# Sheet1.net
KiCad netlist of a schematic drawn in Altium Designer
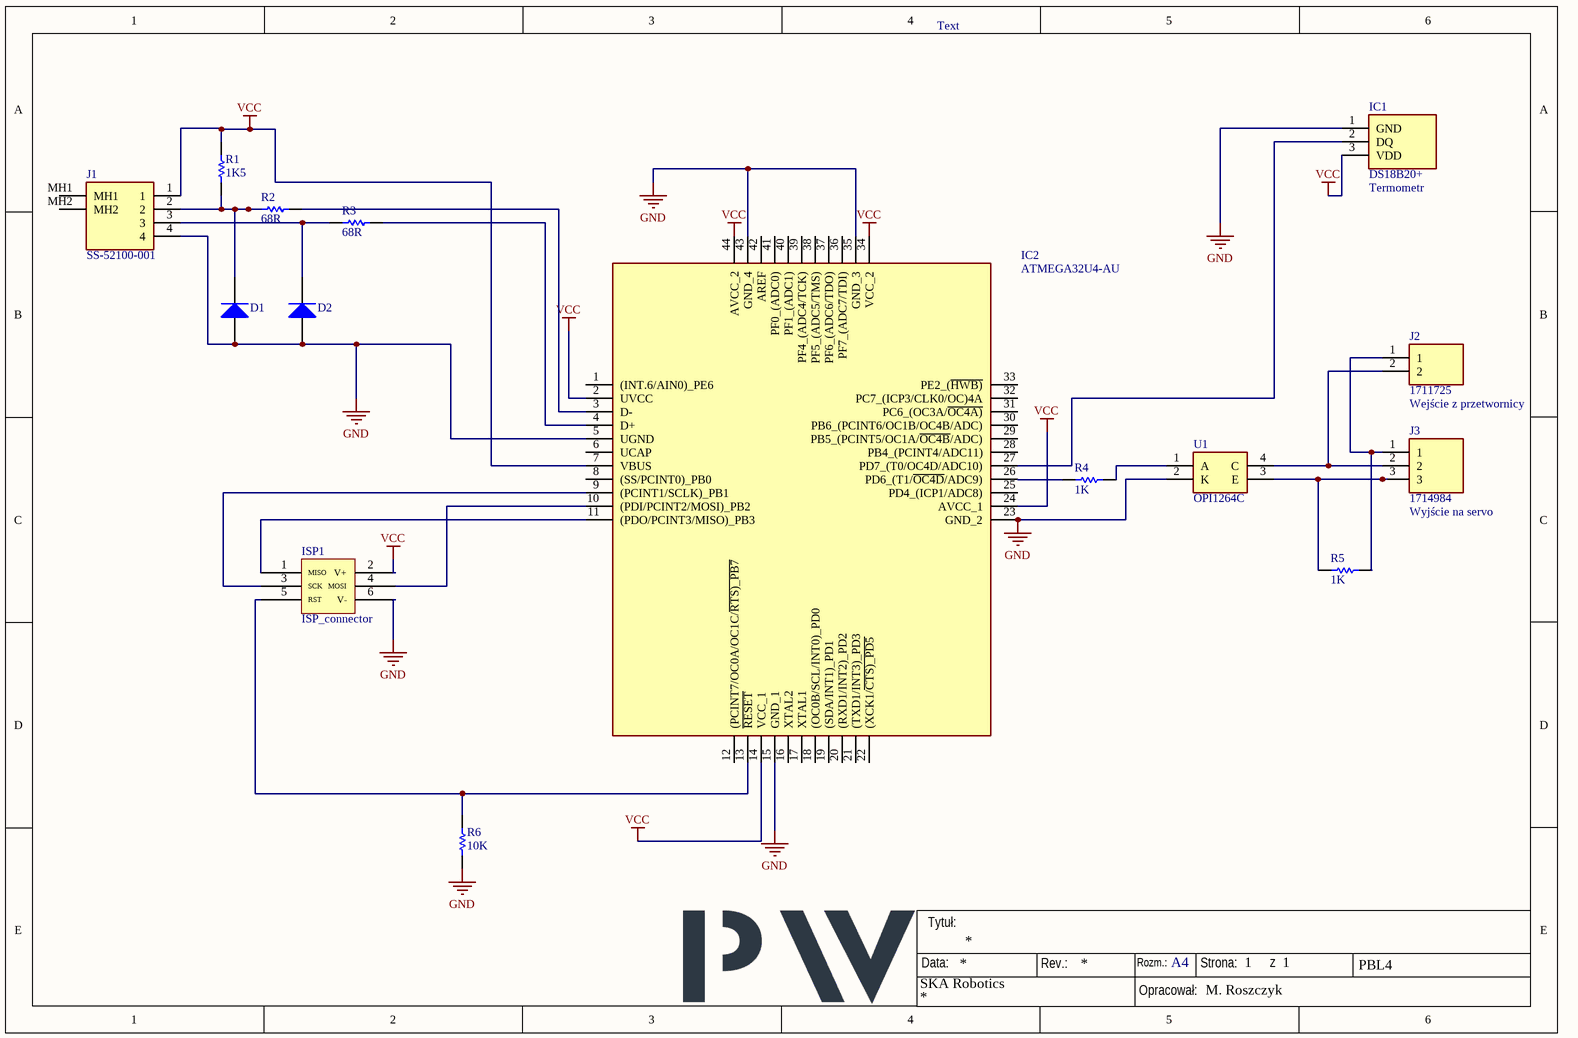
[diagram p0: Sheet1.SchDoc]

(export (version "E")
  (design (tool "Eeschema 10.0.6"))
  (components
    (comp (ref "D1") (value "Diode") (libsource (lib "Simulation Generic Components") (part "Diode")))
    (comp (ref "D2") (value "Diode") (libsource (lib "Simulation Generic Components") (part "Diode")))
    (comp (ref "IC1")
      (value "DS18B20+")
      (footprint "SamacSys:DS18B20")
      (description "Integrated Circuit")
      (fields (field (name "MOUSER PART NUMBER") "700-DS18B20+"))
      (libsource (lib "*") (part "DS18B20+"))
    )
    (comp (ref "IC2")
      (value "ATMEGA32U4-AU")
      (footprint "SamacSys:QFP80P1200X1200X120-44N")
      (description "Integrated Circuit")
      (fields (field (name "MOUSER PART NUMBER") "556-ATMEGA32U4-AU"))
      (libsource (lib "*") (part "ATMEGA32U4-AU"))
    )
    (comp (ref "ISP1") (value "ISP_connector") (libsource (lib "chwytak-schlib") (part "ISP_connector")))
    (comp (ref "J1")
      (value "SS-52100-001")
      (footprint "SamacSys:SS52100001")
      (description "Connector")
      (fields (field (name "MOUSER PART NUMBER") "530-SS-52100-001"))
      (libsource (lib "*") (part "SS-52100-001"))
    )
    (comp (ref "J2")
      (value "1711725")
      (footprint "SamacSys:1711725")
      (description "Connector")
      (fields (field (name "MOUSER PART NUMBER") "651-1711725"))
      (libsource (lib "*") (part "1711725"))
    )
    (comp (ref "J3")
      (value "1714984")
      (footprint "SamacSys:1714984")
      (description "Connector")
      (fields (field (name "MOUSER PART NUMBER") "651-1714984"))
      (libsource (lib "*") (part "1714984"))
    )
    (comp (ref "R1")
      (value "1K5")
      (description "Resistor")
      (libsource (lib "Simulation Generic Components") (part "Resistor"))
    )
    (comp (ref "R2")
      (value "68R")
      (description "Resistor")
      (libsource (lib "Simulation Generic Components") (part "Resistor"))
    )
    (comp (ref "R3")
      (value "68R")
      (description "Resistor")
      (libsource (lib "Simulation Generic Components") (part "Resistor"))
    )
    (comp (ref "R4")
      (value "1K")
      (description "Resistor")
      (libsource (lib "Simulation Generic Components") (part "Resistor"))
    )
    (comp (ref "R5")
      (value "1K")
      (description "Resistor")
      (libsource (lib "Simulation Generic Components") (part "Resistor"))
    )
    (comp (ref "R6")
      (value "10K")
      (footprint "AXIAL-0.3")
      (description "Resistor")
      (fields (field (name "PUBLISHER") "Altium Limited"))
      (libsource (lib "Miscellaneous Devices") (part "Res1"))
    )
    (comp (ref "U1")
      (value "OPI1264C")
      (footprint "SamacSys:OPI1264C")
      (description "Undefined or Miscellaneous")
      (fields (field (name "MOUSER PART NUMBER") "828-OPI1264C"))
      (libsource (lib "*") (part "OPI1264C"))
    )
  )
  (nets
    (net (code "1") (name "GND") (class "Default")
      (node (ref "D1") (pin "1") (pinfunction "A_1") (pintype "passive"))
      (node (ref "D2") (pin "1") (pinfunction "A_1") (pintype "passive"))
      (node (ref "IC1") (pin "1") (pinfunction "GND_1") (pintype "passive"))
      (node (ref "IC2") (pin "15") (pinfunction "GND_1_15") (pintype "passive"))
      (node (ref "IC2") (pin "23") (pinfunction "GND_2_23") (pintype "passive"))
      (node (ref "IC2") (pin "35") (pinfunction "GND_3_35") (pintype "passive"))
      (node (ref "IC2") (pin "43") (pinfunction "GND_4_43") (pintype "passive"))
      (node (ref "IC2") (pin "5") (pinfunction "UGND_5") (pintype "passive"))
      (node (ref "ISP1") (pin "6") (pinfunction "V-_6") (pintype "passive"))
      (node (ref "J1") (pin "4") (pinfunction "4_4") (pintype "passive"))
      (node (ref "R6") (pin "1") (pinfunction "1_1") (pintype "passive"))
      (node (ref "U1") (pin "2") (pinfunction "K_2") (pintype "passive"))
    )
    (net (code "2") (name "Net-(D1-K)") (class "Default")
      (node (ref "D1") (pin "2") (pinfunction "K_2") (pintype "passive"))
      (node (ref "J1") (pin "2") (pinfunction "2_2") (pintype "passive"))
      (node (ref "R1") (pin "1") (pinfunction "1_1") (pintype "passive"))
      (node (ref "R2") (pin "1") (pinfunction "1_1") (pintype "passive"))
    )
    (net (code "3") (name "Net-(D2-K)") (class "Default")
      (node (ref "D2") (pin "2") (pinfunction "K_2") (pintype "passive"))
      (node (ref "J1") (pin "3") (pinfunction "3_3") (pintype "passive"))
      (node (ref "R3") (pin "1") (pinfunction "1_1") (pintype "passive"))
    )
    (net (code "4") (name "Net-(IC1-DQ)") (class "Default")
      (node (ref "IC1") (pin "2") (pinfunction "DQ_2") (pintype "passive"))
      (node (ref "IC2") (pin "27") (pinfunction "PD7_(T0/OC4D/ADC10)_27") (pintype "passive"))
    )
    (net (code "5") (name "Net-(IC2-(PCINT1{slash}SCLK)_PB1)") (class "Default")
      (node (ref "IC2") (pin "9") (pinfunction "(PCINT1/SCLK)_PB1_9") (pintype "passive"))
      (node (ref "ISP1") (pin "3") (pinfunction "SCK_3") (pintype "passive"))
    )
    (net (code "6") (name "Net-(IC2-(PDI{slash}PCINT2{slash}MOSI)_PB2)") (class "Default")
      (node (ref "IC2") (pin "10") (pinfunction "(PDI/PCINT2/MOSI)_PB2_10") (pintype "passive"))
      (node (ref "ISP1") (pin "4") (pinfunction "MOSI_4") (pintype "passive"))
    )
    (net (code "7") (name "Net-(IC2-(PDO{slash}PCINT3{slash}MISO)_PB3)") (class "Default")
      (node (ref "IC2") (pin "11") (pinfunction "(PDO/PCINT3/MISO)_PB3_11") (pintype "passive"))
      (node (ref "ISP1") (pin "1") (pinfunction "MISO_1") (pintype "passive"))
    )
    (net (code "8") (name "Net-(IC2-D+)") (class "Default")
      (node (ref "IC2") (pin "4") (pinfunction "D+_4") (pintype "passive"))
      (node (ref "R3") (pin "2") (pinfunction "2_2") (pintype "passive"))
    )
    (net (code "9") (name "Net-(IC2-D-)") (class "Default")
      (node (ref "IC2") (pin "3") (pinfunction "D-_3") (pintype "passive"))
      (node (ref "R2") (pin "2") (pinfunction "2_2") (pintype "passive"))
    )
    (net (code "10") (name "Net-(IC2-PD6_(T1{slash}~{OC4D}{slash}ADC9))") (class "Default")
      (node (ref "IC2") (pin "26") (pinfunction "PD6_(T1/~{OC4D}/ADC9)_26") (pintype "passive"))
      (node (ref "R4") (pin "1") (pinfunction "1_1") (pintype "passive"))
    )
    (net (code "11") (name "Net-(IC2-~{RESET})") (class "Default")
      (node (ref "IC2") (pin "13") (pinfunction "~{RESET}_13") (pintype "passive"))
      (node (ref "ISP1") (pin "5") (pinfunction "RST_5") (pintype "passive"))
      (node (ref "R6") (pin "2") (pinfunction "2_2") (pintype "passive"))
    )
    (net (code "12") (name "Net-(J2-Pad1)") (class "Default")
      (node (ref "J2") (pin "1") (pinfunction "1_1") (pintype "passive"))
      (node (ref "J3") (pin "1") (pinfunction "1_1") (pintype "passive"))
      (node (ref "R5") (pin "2") (pinfunction "2_2") (pintype "passive"))
    )
    (net (code "13") (name "Net-(U1-A)") (class "Default")
      (node (ref "R4") (pin "2") (pinfunction "2_2") (pintype "passive"))
      (node (ref "U1") (pin "1") (pinfunction "A_1") (pintype "passive"))
    )
    (net (code "14") (name "Net-(U1-C)") (class "Default")
      (node (ref "J2") (pin "2") (pinfunction "2_2") (pintype "passive"))
      (node (ref "J3") (pin "2") (pinfunction "2_2") (pintype "passive"))
      (node (ref "U1") (pin "4") (pinfunction "C_4") (pintype "passive"))
    )
    (net (code "15") (name "Net-(U1-E)") (class "Default")
      (node (ref "J3") (pin "3") (pinfunction "3_3") (pintype "passive"))
      (node (ref "R5") (pin "1") (pinfunction "1_1") (pintype "passive"))
      (node (ref "U1") (pin "3") (pinfunction "E_3") (pintype "passive"))
    )
    (net (code "16") (name "VCC") (class "Default")
      (node (ref "IC1") (pin "3") (pinfunction "VDD_3") (pintype "passive"))
      (node (ref "IC2") (pin "14") (pinfunction "VCC_1_14") (pintype "passive"))
      (node (ref "IC2") (pin "2") (pinfunction "UVCC_2") (pintype "passive"))
      (node (ref "IC2") (pin "24") (pinfunction "AVCC_1_24") (pintype "passive"))
      (node (ref "IC2") (pin "34") (pinfunction "VCC_2_34") (pintype "passive"))
      (node (ref "IC2") (pin "44") (pinfunction "AVCC_2_44") (pintype "passive"))
      (node (ref "IC2") (pin "7") (pinfunction "VBUS_7") (pintype "passive"))
      (node (ref "ISP1") (pin "2") (pinfunction "V+_2") (pintype "passive"))
      (node (ref "J1") (pin "1") (pinfunction "1_1") (pintype "passive"))
      (node (ref "R1") (pin "2") (pinfunction "2_2") (pintype "passive"))
    )
    (net (code "17") (name "unconnected-(IC2-(INT.6{slash}AIN0)_PE6-Pad1)") (class "Default")
      (node (ref "IC2") (pin "1") (pinfunction "(INT.6/AIN0)_PE6_1") (pintype "passive"))
    )
    (net (code "18") (name "unconnected-(IC2-(OC0B{slash}SCL{slash}INT0)_PD0-Pad18)") (class "Default")
      (node (ref "IC2") (pin "18") (pinfunction "(OC0B/SCL/INT0)_PD0_18") (pintype "passive"))
    )
    (net (code "19") (name "unconnected-(IC2-(PCINT7{slash}OC0A{slash}OC1C{slash}~{RTS)_PB7}-Pad12)") (class "Default")
      (node (ref "IC2") (pin "12") (pinfunction "(PCINT7/OC0A/OC1C/~{RTS)_PB7}_12") (pintype "passive"))
    )
    (net (code "20") (name "unconnected-(IC2-(RXD1{slash}INT2)_PD2-Pad20)") (class "Default")
      (node (ref "IC2") (pin "20") (pinfunction "(RXD1/INT2)_PD2_20") (pintype "passive"))
    )
    (net (code "21") (name "unconnected-(IC2-(SDA{slash}INT1)_PD1-Pad19)") (class "Default")
      (node (ref "IC2") (pin "19") (pinfunction "(SDA/INT1)_PD1_19") (pintype "passive"))
    )
    (net (code "22") (name "unconnected-(IC2-(SS{slash}PCINT0)_PB0-Pad8)") (class "Default")
      (node (ref "IC2") (pin "8") (pinfunction "(SS/PCINT0)_PB0_8") (pintype "passive"))
    )
    (net (code "23") (name "unconnected-(IC2-(TXD1{slash}INT3)_PD3-Pad21)") (class "Default")
      (node (ref "IC2") (pin "21") (pinfunction "(TXD1/INT3)_PD3_21") (pintype "passive"))
    )
    (net (code "24") (name "unconnected-(IC2-(XCK1{slash}~{CTS)_PD5}-Pad22)") (class "Default")
      (node (ref "IC2") (pin "22") (pinfunction "(XCK1/~{CTS)_PD5}_22") (pintype "passive"))
    )
    (net (code "25") (name "unconnected-(IC2-AREF-Pad42)") (class "Default")
      (node (ref "IC2") (pin "42") (pinfunction "AREF_42") (pintype "passive"))
    )
    (net (code "26") (name "unconnected-(IC2-PB4_(PCINT4{slash}ADC11)-Pad28)") (class "Default")
      (node (ref "IC2") (pin "28") (pinfunction "PB4_(PCINT4/ADC11)_28") (pintype "passive"))
    )
    (net (code "27") (name "unconnected-(IC2-PB5_(PCINT5{slash}OC1A{slash}~{OC4B}{slash}ADC)-Pad29)") (class "Default")
      (node (ref "IC2") (pin "29") (pinfunction "PB5_(PCINT5/OC1A/~{OC4B}/ADC)_29") (pintype "passive"))
    )
    (net (code "28") (name "unconnected-(IC2-PB6_(PCINT6{slash}OC1B{slash}OC4B{slash}ADC)-Pad30)") (class "Default")
      (node (ref "IC2") (pin "30") (pinfunction "PB6_(PCINT6/OC1B/OC4B/ADC)_30") (pintype "passive"))
    )
    (net (code "29") (name "unconnected-(IC2-PC6_(OC3A{slash}~{OC4A)}-Pad31)") (class "Default")
      (node (ref "IC2") (pin "31") (pinfunction "PC6_(OC3A/~{OC4A)}_31") (pintype "passive"))
    )
    (net (code "30") (name "unconnected-(IC2-PC7_(ICP3{slash}CLK0{slash}OC)4A-Pad32)") (class "Default")
      (node (ref "IC2") (pin "32") (pinfunction "PC7_(ICP3/CLK0/OC)4A_32") (pintype "passive"))
    )
    (net (code "31") (name "unconnected-(IC2-PD4_(ICP1{slash}ADC8)-Pad25)") (class "Default")
      (node (ref "IC2") (pin "25") (pinfunction "PD4_(ICP1/ADC8)_25") (pintype "passive"))
    )
    (net (code "32") (name "unconnected-(IC2-PE2_(~{HWB)}-Pad33)") (class "Default")
      (node (ref "IC2") (pin "33") (pinfunction "PE2_(~{HWB)}_33") (pintype "passive"))
    )
    (net (code "33") (name "unconnected-(IC2-PF0_(ADC0)-Pad41)") (class "Default")
      (node (ref "IC2") (pin "41") (pinfunction "PF0_(ADC0)_41") (pintype "passive"))
    )
    (net (code "34") (name "unconnected-(IC2-PF1_(ADC1)-Pad40)") (class "Default")
      (node (ref "IC2") (pin "40") (pinfunction "PF1_(ADC1)_40") (pintype "passive"))
    )
    (net (code "35") (name "unconnected-(IC2-PF4_(ADC4{slash}TCK)-Pad39)") (class "Default")
      (node (ref "IC2") (pin "39") (pinfunction "PF4_(ADC4/TCK)_39") (pintype "passive"))
    )
    (net (code "36") (name "unconnected-(IC2-PF5_(ADC5{slash}TMS)-Pad38)") (class "Default")
      (node (ref "IC2") (pin "38") (pinfunction "PF5_(ADC5/TMS)_38") (pintype "passive"))
    )
    (net (code "37") (name "unconnected-(IC2-PF6_(ADC6{slash}TDO)-Pad37)") (class "Default")
      (node (ref "IC2") (pin "37") (pinfunction "PF6_(ADC6/TDO)_37") (pintype "passive"))
    )
    (net (code "38") (name "unconnected-(IC2-PF7_(ADC7{slash}TDI)-Pad36)") (class "Default")
      (node (ref "IC2") (pin "36") (pinfunction "PF7_(ADC7/TDI)_36") (pintype "passive"))
    )
    (net (code "39") (name "unconnected-(IC2-UCAP-Pad6)") (class "Default")
      (node (ref "IC2") (pin "6") (pinfunction "UCAP_6") (pintype "passive"))
    )
    (net (code "40") (name "unconnected-(IC2-XTAL1-Pad17)") (class "Default")
      (node (ref "IC2") (pin "17") (pinfunction "XTAL1_17") (pintype "passive"))
    )
    (net (code "41") (name "unconnected-(IC2-XTAL2-Pad16)") (class "Default")
      (node (ref "IC2") (pin "16") (pinfunction "XTAL2_16") (pintype "passive"))
    )
    (net (code "42") (name "unconnected-(J1-PadMH1)") (class "Default")
      (node (ref "J1") (pin "MH1") (pinfunction "MH1_MH1") (pintype "passive"))
    )
    (net (code "43") (name "unconnected-(J1-PadMH2)") (class "Default")
      (node (ref "J1") (pin "MH2") (pinfunction "MH2_MH2") (pintype "passive"))
    )
  )
)
